# Sheet1.net
KiCad netlist of a schematic drawn in Altium Designer
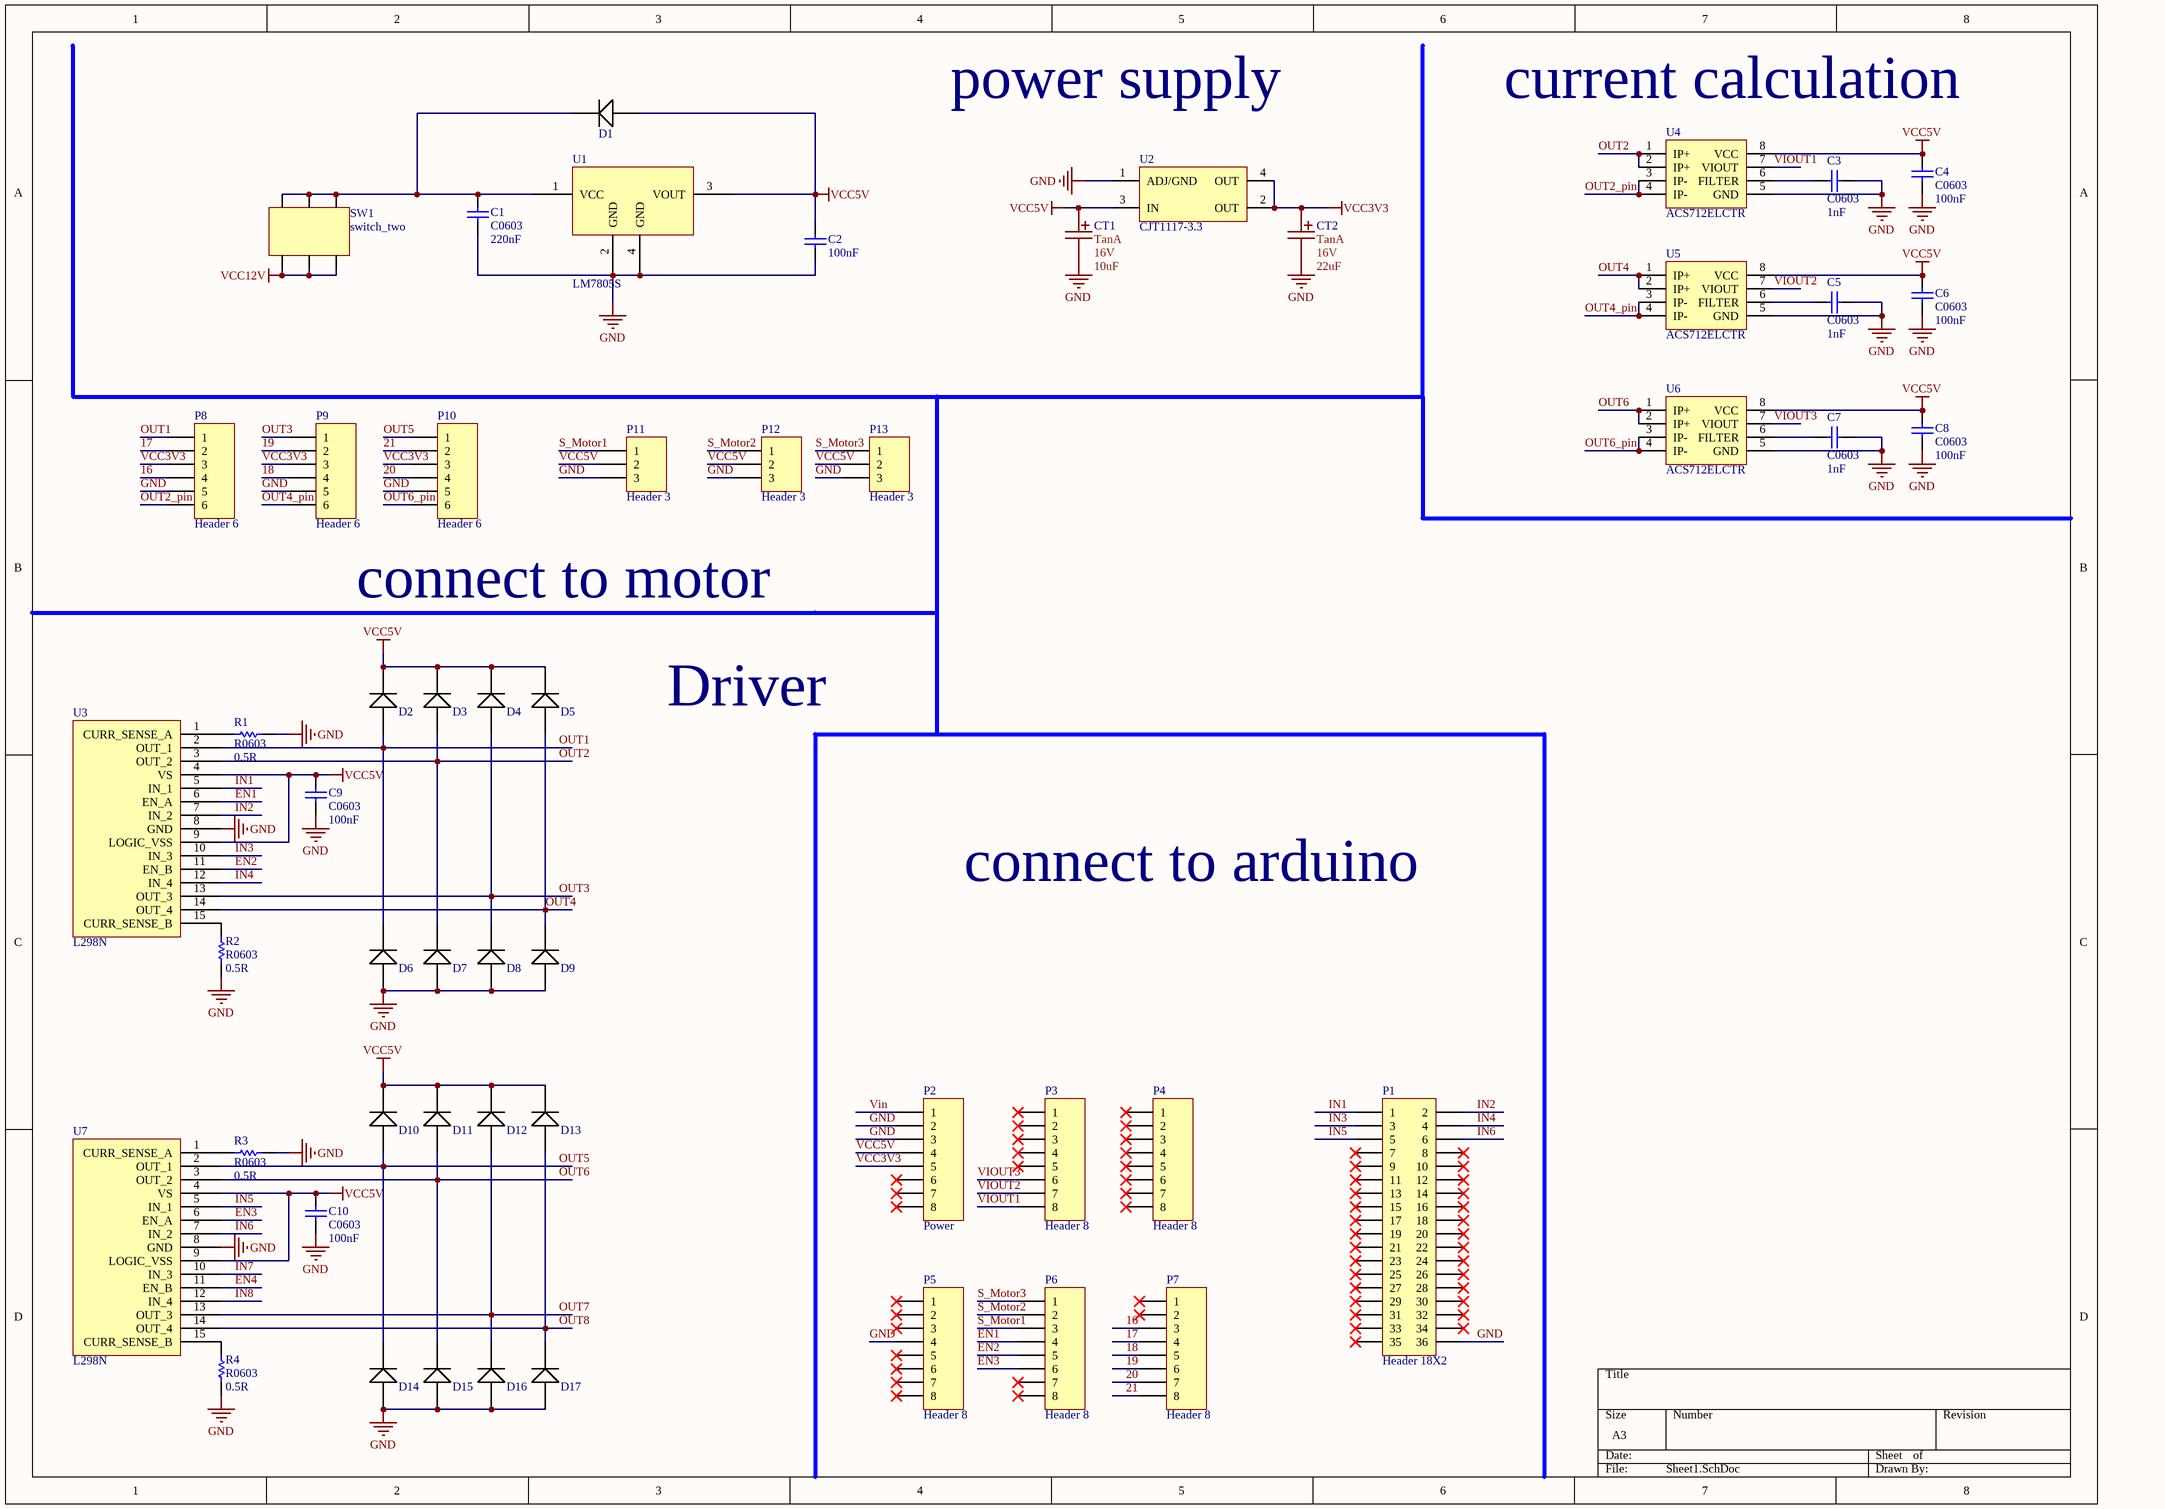
[diagram p0: Sheet1.SchDoc]

(export (version "E")
  (design (tool "Eeschema 10.0.6"))
  (components
    (comp (ref "C1")
      (value "220nF")
      (footprint "C0603_160X80X140L35N")
      (description "0603 SMT MLCC Capacitor")
      (fields
        (field (name "VOLTAGE") "50V")
        (field (name "TOLERANCE") "10%")
        (field (name "CASE/PACKAGE") "C0603")
        (field (name "PUBLISHER") "Altium Limited")
      )
      (libsource (lib "ayaya0lib") (part "Cap0603"))
    )
    (comp (ref "C2")
      (value "100nF")
      (footprint "C0402_100X50X140L30N")
      (description "SMT MLCC Capacitor")
      (fields (field (name "Comment") "Capacitor") (field (name "PUBLISHER") "Altium Limited"))
      (libsource (lib "ayayalib") (part "Cap1"))
    )
    (comp (ref "C3")
      (value "1nF")
      (footprint "C0603_160X80X140L35N")
      (description "0603 SMT MLCC Capacitor")
      (fields
        (field (name "VOLTAGE") "50V")
        (field (name "TOLERANCE") "10%")
        (field (name "CASE/PACKAGE") "C0603")
        (field (name "PUBLISHER") "Altium Limited")
      )
      (libsource (lib "ayaya0lib") (part "Cap0603"))
    )
    (comp (ref "C4")
      (value "100nF")
      (footprint "C0603_160X80X140L35N")
      (description "0603 SMT MLCC Capacitor")
      (fields
        (field (name "VOLTAGE") "50V")
        (field (name "TOLERANCE") "10%")
        (field (name "CASE/PACKAGE") "C0603")
        (field (name "PUBLISHER") "Altium Limited")
      )
      (libsource (lib "ayaya0lib") (part "Cap0603"))
    )
    (comp (ref "C5")
      (value "1nF")
      (footprint "C0603_160X80X140L35N")
      (description "0603 SMT MLCC Capacitor")
      (fields
        (field (name "VOLTAGE") "50V")
        (field (name "TOLERANCE") "10%")
        (field (name "CASE/PACKAGE") "C0603")
        (field (name "PUBLISHER") "Altium Limited")
      )
      (libsource (lib "ayaya0lib") (part "Cap0603"))
    )
    (comp (ref "C6")
      (value "100nF")
      (footprint "C0603_160X80X140L35N")
      (description "0603 SMT MLCC Capacitor")
      (fields
        (field (name "VOLTAGE") "50V")
        (field (name "TOLERANCE") "10%")
        (field (name "CASE/PACKAGE") "C0603")
        (field (name "PUBLISHER") "Altium Limited")
      )
      (libsource (lib "ayaya0lib") (part "Cap0603"))
    )
    (comp (ref "C7")
      (value "1nF")
      (footprint "C0603_160X80X140L35N")
      (description "0603 SMT MLCC Capacitor")
      (fields
        (field (name "VOLTAGE") "50V")
        (field (name "TOLERANCE") "10%")
        (field (name "CASE/PACKAGE") "C0603")
        (field (name "PUBLISHER") "Altium Limited")
      )
      (libsource (lib "ayaya0lib") (part "Cap0603"))
    )
    (comp (ref "C8")
      (value "100nF")
      (footprint "C0603_160X80X140L35N")
      (description "0603 SMT MLCC Capacitor")
      (fields
        (field (name "VOLTAGE") "50V")
        (field (name "TOLERANCE") "10%")
        (field (name "CASE/PACKAGE") "C0603")
        (field (name "PUBLISHER") "Altium Limited")
      )
      (libsource (lib "ayaya0lib") (part "Cap0603"))
    )
    (comp (ref "C9")
      (value "100nF")
      (footprint "C0603_160X80X140L35N")
      (description "0603 SMT MLCC Capacitor")
      (fields
        (field (name "VOLTAGE") "50V")
        (field (name "TOLERANCE") "10%")
        (field (name "CASE/PACKAGE") "C0603")
        (field (name "PUBLISHER") "Altium Limited")
      )
      (libsource (lib "ayaya0lib") (part "Cap0603"))
    )
    (comp (ref "C10")
      (value "100nF")
      (footprint "C0603_160X80X140L35N")
      (description "0603 SMT MLCC Capacitor")
      (fields
        (field (name "VOLTAGE") "50V")
        (field (name "TOLERANCE") "10%")
        (field (name "CASE/PACKAGE") "C0603")
        (field (name "PUBLISHER") "Altium Limited")
      )
      (libsource (lib "ayaya0lib") (part "Cap0603"))
    )
    (comp (ref "CT1")
      (value "10uF")
      (footprint "CTA_320X160X180L85X120N")
      (description "A case Tantalum Capacitors")
      (fields
        (field (name "TOLERANCE") "10%")
        (field (name "CASE/PACKAGE") "TanA")
        (field (name "VOLTAGE") "16V")
      )
      (libsource (lib "ayaya0lib") (part "Cap_TanA"))
    )
    (comp (ref "CT2")
      (value "22uF")
      (footprint "CTA_320X160X180L85X120N")
      (description "A case Tantalum Capacitors")
      (fields
        (field (name "TOLERANCE") "10%")
        (field (name "CASE/PACKAGE") "TanA")
        (field (name "VOLTAGE") "16V")
      )
      (libsource (lib "ayaya0lib") (part "Cap_TanA"))
    )
    (comp (ref "D1") (value "diode") (footprint "diode") (libsource (lib "driver_L289N") (part "diode")))
    (comp (ref "D2") (value "diode") (footprint "diode") (libsource (lib "driver_L289N") (part "diode")))
    (comp (ref "D3") (value "diode") (footprint "diode") (libsource (lib "driver_L289N") (part "diode")))
    (comp (ref "D4") (value "diode") (footprint "diode") (libsource (lib "driver_L289N") (part "diode")))
    (comp (ref "D5") (value "diode") (footprint "diode") (libsource (lib "driver_L289N") (part "diode")))
    (comp (ref "D6") (value "diode") (footprint "diode") (libsource (lib "driver_L289N") (part "diode")))
    (comp (ref "D7") (value "diode") (footprint "diode") (libsource (lib "driver_L289N") (part "diode")))
    (comp (ref "D8") (value "diode") (footprint "diode") (libsource (lib "driver_L289N") (part "diode")))
    (comp (ref "D9") (value "diode") (footprint "diode") (libsource (lib "driver_L289N") (part "diode")))
    (comp (ref "D10") (value "diode") (footprint "diode") (libsource (lib "driver_L289N") (part "diode")))
    (comp (ref "D11") (value "diode") (footprint "diode") (libsource (lib "driver_L289N") (part "diode")))
    (comp (ref "D12") (value "diode") (footprint "diode") (libsource (lib "driver_L289N") (part "diode")))
    (comp (ref "D13") (value "diode") (footprint "diode") (libsource (lib "driver_L289N") (part "diode")))
    (comp (ref "D14") (value "diode") (footprint "diode") (libsource (lib "driver_L289N") (part "diode")))
    (comp (ref "D15") (value "diode") (footprint "diode") (libsource (lib "driver_L289N") (part "diode")))
    (comp (ref "D16") (value "diode") (footprint "diode") (libsource (lib "driver_L289N") (part "diode")))
    (comp (ref "D17") (value "diode") (footprint "diode") (libsource (lib "driver_L289N") (part "diode")))
    (comp (ref "P1")
      (value "Header 18X2")
      (footprint "HDR2X18")
      (description "Header, 18-Pin, Dual row")
      (fields (field (name "PUBLISHER") "Altium Limited"))
      (libsource (lib "Miscellaneous Connectors") (part "Header 18X2"))
    )
    (comp (ref "P2")
      (value "Power")
      (footprint "HDR1X8")
      (description "Header, 8-Pin")
      (fields (field (name "PUBLISHER") "Altium Limited"))
      (libsource (lib "Miscellaneous Connectors") (part "Header 8"))
    )
    (comp (ref "P3")
      (value "Header 8")
      (footprint "HDR1X8")
      (description "Header, 8-Pin")
      (fields (field (name "PUBLISHER") "Altium Limited"))
      (libsource (lib "Miscellaneous Connectors") (part "Header 8"))
    )
    (comp (ref "P4")
      (value "Header 8")
      (footprint "HDR1X8")
      (description "Header, 8-Pin")
      (fields (field (name "PUBLISHER") "Altium Limited"))
      (libsource (lib "Miscellaneous Connectors") (part "Header 8"))
    )
    (comp (ref "P5")
      (value "Header 8")
      (footprint "HDR1X8")
      (description "Header, 8-Pin")
      (fields (field (name "PUBLISHER") "Altium Limited"))
      (libsource (lib "Miscellaneous Connectors") (part "Header 8"))
    )
    (comp (ref "P6")
      (value "Header 8")
      (footprint "HDR1X8")
      (description "Header, 8-Pin")
      (fields (field (name "PUBLISHER") "Altium Limited"))
      (libsource (lib "Miscellaneous Connectors") (part "Header 8"))
    )
    (comp (ref "P7")
      (value "Header 8")
      (footprint "HDR1X8")
      (description "Header, 8-Pin")
      (fields (field (name "PUBLISHER") "Altium Limited"))
      (libsource (lib "Miscellaneous Connectors") (part "Header 8"))
    )
    (comp (ref "P8")
      (value "Header 6")
      (footprint "HDR1X6")
      (description "Header, 6-Pin")
      (fields (field (name "PUBLISHER") "Altium Limited"))
      (libsource (lib "Miscellaneous Connectors") (part "Header 6"))
    )
    (comp (ref "P9")
      (value "Header 6")
      (footprint "HDR1X6")
      (description "Header, 6-Pin")
      (fields (field (name "PUBLISHER") "Altium Limited"))
      (libsource (lib "Miscellaneous Connectors") (part "Header 6"))
    )
    (comp (ref "P10")
      (value "Header 6")
      (footprint "HDR1X6")
      (description "Header, 6-Pin")
      (fields (field (name "PUBLISHER") "Altium Limited"))
      (libsource (lib "Miscellaneous Connectors") (part "Header 6"))
    )
    (comp (ref "P11")
      (value "Header 3")
      (footprint "HDR1X3")
      (description "Header, 3-Pin")
      (fields (field (name "PUBLISHER") "Altium Limited"))
      (libsource (lib "Miscellaneous Connectors") (part "Header 3"))
    )
    (comp (ref "P12")
      (value "Header 3")
      (footprint "HDR1X3")
      (description "Header, 3-Pin")
      (fields (field (name "PUBLISHER") "Altium Limited"))
      (libsource (lib "Miscellaneous Connectors") (part "Header 3"))
    )
    (comp (ref "P13")
      (value "Header 3")
      (footprint "HDR1X3")
      (description "Header, 3-Pin")
      (fields (field (name "PUBLISHER") "Altium Limited"))
      (libsource (lib "Miscellaneous Connectors") (part "Header 3"))
    )
    (comp (ref "R1")
      (value "0.5R")
      (footprint "R0603_160X80X140L35N")
      (description "0603 SMT Resistor")
      (fields
        (field (name "TOLERANCE") "1%")
        (field (name "CASE/PACKAGE") "R0603")
        (field (name "PUBLISHER") "Altium Limited")
      )
      (libsource (lib "ayaya0lib") (part "Res0603"))
    )
    (comp (ref "R2")
      (value "0.5R")
      (footprint "R0603_160X80X140L35N")
      (description "0603 SMT Resistor")
      (fields
        (field (name "TOLERANCE") "1%")
        (field (name "CASE/PACKAGE") "R0603")
        (field (name "PUBLISHER") "Altium Limited")
      )
      (libsource (lib "ayaya0lib") (part "Res0603"))
    )
    (comp (ref "R3")
      (value "0.5R")
      (footprint "R0603_160X80X140L35N")
      (description "0603 SMT Resistor")
      (fields
        (field (name "TOLERANCE") "1%")
        (field (name "CASE/PACKAGE") "R0603")
        (field (name "PUBLISHER") "Altium Limited")
      )
      (libsource (lib "ayaya0lib") (part "Res0603"))
    )
    (comp (ref "R4")
      (value "0.5R")
      (footprint "R0603_160X80X140L35N")
      (description "0603 SMT Resistor")
      (fields
        (field (name "TOLERANCE") "1%")
        (field (name "CASE/PACKAGE") "R0603")
        (field (name "PUBLISHER") "Altium Limited")
      )
      (libsource (lib "ayaya0lib") (part "Res0603"))
    )
    (comp (ref "SW1")
      (value "switch_two")
      (footprint "switch_two")
      (libsource (lib "driver_L289N") (part "switch_two"))
    )
    (comp (ref "U1")
      (value "LM7805S")
      (footprint "LM7805S")
      (libsource (lib "driver_L289N") (part "LM7805S"))
    )
    (comp (ref "U2")
      (value "CJT1117-3.3")
      (footprint "CJT1117")
      (libsource (lib "driver_L289N") (part "CJT1117-3.3"))
    )
    (comp (ref "U3")
      (value "L298N")
      (footprint "PCBComponent_1")
      (libsource (lib "driver_L289N") (part "L298N"))
    )
    (comp (ref "U4")
      (value "ACS712ELCTR")
      (footprint "ACS712ELCTR")
      (libsource (lib "driver_L289N") (part "ACS712ELCTR"))
    )
    (comp (ref "U5")
      (value "ACS712ELCTR")
      (footprint "ACS712ELCTR")
      (libsource (lib "driver_L289N") (part "ACS712ELCTR"))
    )
    (comp (ref "U6")
      (value "ACS712ELCTR")
      (footprint "ACS712ELCTR")
      (libsource (lib "driver_L289N") (part "ACS712ELCTR"))
    )
    (comp (ref "U7")
      (value "L298N")
      (footprint "PCBComponent_1")
      (libsource (lib "driver_L289N") (part "L298N"))
    )
  )
  (nets
    (net (code "1") (name "/16") (class "Default")
      (node (ref "P7") (pin "3") (pinfunction "3_3") (pintype "passive"))
      (node (ref "P8") (pin "4") (pinfunction "4_4") (pintype "passive"))
    )
    (net (code "2") (name "/17") (class "Default")
      (node (ref "P7") (pin "4") (pinfunction "4_4") (pintype "passive"))
      (node (ref "P8") (pin "2") (pinfunction "2_2") (pintype "passive"))
    )
    (net (code "3") (name "/18") (class "Default")
      (node (ref "P7") (pin "5") (pinfunction "5_5") (pintype "passive"))
      (node (ref "P9") (pin "4") (pinfunction "4_4") (pintype "passive"))
    )
    (net (code "4") (name "/19") (class "Default")
      (node (ref "P7") (pin "6") (pinfunction "6_6") (pintype "passive"))
      (node (ref "P9") (pin "2") (pinfunction "2_2") (pintype "passive"))
    )
    (net (code "5") (name "/20") (class "Default")
      (node (ref "P10") (pin "4") (pinfunction "4_4") (pintype "passive"))
      (node (ref "P7") (pin "7") (pinfunction "7_7") (pintype "passive"))
    )
    (net (code "6") (name "/21") (class "Default")
      (node (ref "P10") (pin "2") (pinfunction "2_2") (pintype "passive"))
      (node (ref "P7") (pin "8") (pinfunction "8_8") (pintype "passive"))
    )
    (net (code "7") (name "/EN1") (class "Default")
      (node (ref "P6") (pin "4") (pinfunction "4_4") (pintype "passive"))
      (node (ref "U3") (pin "6") (pinfunction "EN_A_6") (pintype "passive"))
    )
    (net (code "8") (name "/EN2") (class "Default")
      (node (ref "P6") (pin "5") (pinfunction "5_5") (pintype "passive"))
      (node (ref "U3") (pin "11") (pinfunction "EN_B_11") (pintype "passive"))
    )
    (net (code "9") (name "/EN3") (class "Default")
      (node (ref "P6") (pin "6") (pinfunction "6_6") (pintype "passive"))
      (node (ref "U7") (pin "6") (pinfunction "EN_A_6") (pintype "passive"))
    )
    (net (code "10") (name "/EN4") (class "Default")
      (node (ref "U7") (pin "11") (pinfunction "EN_B_11") (pintype "passive"))
    )
    (net (code "11") (name "/IN1") (class "Default")
      (node (ref "P1") (pin "1") (pinfunction "1_1") (pintype "passive"))
      (node (ref "U3") (pin "5") (pinfunction "IN_1_5") (pintype "passive"))
    )
    (net (code "12") (name "/IN2") (class "Default")
      (node (ref "P1") (pin "2") (pinfunction "2_2") (pintype "passive"))
      (node (ref "U3") (pin "7") (pinfunction "IN_2_7") (pintype "passive"))
    )
    (net (code "13") (name "/IN3") (class "Default")
      (node (ref "P1") (pin "3") (pinfunction "3_3") (pintype "passive"))
      (node (ref "U3") (pin "10") (pinfunction "IN_3_10") (pintype "passive"))
    )
    (net (code "14") (name "/IN4") (class "Default")
      (node (ref "P1") (pin "4") (pinfunction "4_4") (pintype "passive"))
      (node (ref "U3") (pin "12") (pinfunction "IN_4_12") (pintype "passive"))
    )
    (net (code "15") (name "/IN5") (class "Default")
      (node (ref "P1") (pin "5") (pinfunction "5_5") (pintype "passive"))
      (node (ref "U7") (pin "5") (pinfunction "IN_1_5") (pintype "passive"))
    )
    (net (code "16") (name "/IN6") (class "Default")
      (node (ref "P1") (pin "6") (pinfunction "6_6") (pintype "passive"))
      (node (ref "U7") (pin "7") (pinfunction "IN_2_7") (pintype "passive"))
    )
    (net (code "17") (name "/IN7") (class "Default")
      (node (ref "U7") (pin "10") (pinfunction "IN_3_10") (pintype "passive"))
    )
    (net (code "18") (name "/IN8") (class "Default")
      (node (ref "U7") (pin "12") (pinfunction "IN_4_12") (pintype "passive"))
    )
    (net (code "19") (name "/OUT1") (class "Default")
      (node (ref "D2") (pin "1") (pinfunction "-_1") (pintype "passive"))
      (node (ref "D6") (pin "2") (pinfunction "+_2") (pintype "passive"))
      (node (ref "P8") (pin "1") (pinfunction "1_1") (pintype "passive"))
      (node (ref "U3") (pin "2") (pinfunction "OUT_1_2") (pintype "passive"))
    )
    (net (code "20") (name "/OUT2") (class "Default")
      (node (ref "D3") (pin "1") (pinfunction "-_1") (pintype "passive"))
      (node (ref "D7") (pin "2") (pinfunction "+_2") (pintype "passive"))
      (node (ref "U3") (pin "3") (pinfunction "OUT_2_3") (pintype "passive"))
      (node (ref "U4") (pin "1") (pinfunction "IP+_1") (pintype "passive"))
      (node (ref "U4") (pin "2") (pinfunction "IP+_2") (pintype "passive"))
    )
    (net (code "21") (name "/OUT2_pin") (class "Default")
      (node (ref "P8") (pin "6") (pinfunction "6_6") (pintype "passive"))
      (node (ref "U4") (pin "3") (pinfunction "IP-_3") (pintype "passive"))
      (node (ref "U4") (pin "4") (pinfunction "IP-_4") (pintype "passive"))
    )
    (net (code "22") (name "/OUT3") (class "Default")
      (node (ref "D4") (pin "1") (pinfunction "-_1") (pintype "passive"))
      (node (ref "D8") (pin "2") (pinfunction "+_2") (pintype "passive"))
      (node (ref "P9") (pin "1") (pinfunction "1_1") (pintype "passive"))
      (node (ref "U3") (pin "13") (pinfunction "OUT_3_13") (pintype "passive"))
    )
    (net (code "23") (name "/OUT4") (class "Default")
      (node (ref "D5") (pin "1") (pinfunction "-_1") (pintype "passive"))
      (node (ref "D9") (pin "2") (pinfunction "+_2") (pintype "passive"))
      (node (ref "U3") (pin "14") (pinfunction "OUT_4_14") (pintype "passive"))
      (node (ref "U5") (pin "1") (pinfunction "IP+_1") (pintype "passive"))
      (node (ref "U5") (pin "2") (pinfunction "IP+_2") (pintype "passive"))
    )
    (net (code "24") (name "/OUT4_pin") (class "Default")
      (node (ref "P9") (pin "6") (pinfunction "6_6") (pintype "passive"))
      (node (ref "U5") (pin "3") (pinfunction "IP-_3") (pintype "passive"))
      (node (ref "U5") (pin "4") (pinfunction "IP-_4") (pintype "passive"))
    )
    (net (code "25") (name "/OUT5") (class "Default")
      (node (ref "D10") (pin "1") (pinfunction "-_1") (pintype "passive"))
      (node (ref "D14") (pin "2") (pinfunction "+_2") (pintype "passive"))
      (node (ref "P10") (pin "1") (pinfunction "1_1") (pintype "passive"))
      (node (ref "U7") (pin "2") (pinfunction "OUT_1_2") (pintype "passive"))
    )
    (net (code "26") (name "/OUT6") (class "Default")
      (node (ref "D11") (pin "1") (pinfunction "-_1") (pintype "passive"))
      (node (ref "D15") (pin "2") (pinfunction "+_2") (pintype "passive"))
      (node (ref "U6") (pin "1") (pinfunction "IP+_1") (pintype "passive"))
      (node (ref "U6") (pin "2") (pinfunction "IP+_2") (pintype "passive"))
      (node (ref "U7") (pin "3") (pinfunction "OUT_2_3") (pintype "passive"))
    )
    (net (code "27") (name "/OUT6_pin") (class "Default")
      (node (ref "P10") (pin "6") (pinfunction "6_6") (pintype "passive"))
      (node (ref "U6") (pin "3") (pinfunction "IP-_3") (pintype "passive"))
      (node (ref "U6") (pin "4") (pinfunction "IP-_4") (pintype "passive"))
    )
    (net (code "28") (name "/OUT7") (class "Default")
      (node (ref "D12") (pin "1") (pinfunction "-_1") (pintype "passive"))
      (node (ref "D16") (pin "2") (pinfunction "+_2") (pintype "passive"))
      (node (ref "U7") (pin "13") (pinfunction "OUT_3_13") (pintype "passive"))
    )
    (net (code "29") (name "/OUT8") (class "Default")
      (node (ref "D13") (pin "1") (pinfunction "-_1") (pintype "passive"))
      (node (ref "D17") (pin "2") (pinfunction "+_2") (pintype "passive"))
      (node (ref "U7") (pin "14") (pinfunction "OUT_4_14") (pintype "passive"))
    )
    (net (code "30") (name "/S_Motor1") (class "Default")
      (node (ref "P11") (pin "1") (pinfunction "1_1") (pintype "passive"))
      (node (ref "P6") (pin "3") (pinfunction "3_3") (pintype "passive"))
    )
    (net (code "31") (name "/S_Motor2") (class "Default")
      (node (ref "P12") (pin "1") (pinfunction "1_1") (pintype "passive"))
      (node (ref "P6") (pin "2") (pinfunction "2_2") (pintype "passive"))
    )
    (net (code "32") (name "/S_Motor3") (class "Default")
      (node (ref "P13") (pin "1") (pinfunction "1_1") (pintype "passive"))
      (node (ref "P6") (pin "1") (pinfunction "1_1") (pintype "passive"))
    )
    (net (code "33") (name "/VIOUT1") (class "Default")
      (node (ref "P3") (pin "8") (pinfunction "8_8") (pintype "passive"))
      (node (ref "U4") (pin "7") (pinfunction "VIOUT_7") (pintype "passive"))
    )
    (net (code "34") (name "/VIOUT2") (class "Default")
      (node (ref "P3") (pin "7") (pinfunction "7_7") (pintype "passive"))
      (node (ref "U5") (pin "7") (pinfunction "VIOUT_7") (pintype "passive"))
    )
    (net (code "35") (name "/VIOUT3") (class "Default")
      (node (ref "P3") (pin "6") (pinfunction "6_6") (pintype "passive"))
      (node (ref "U6") (pin "7") (pinfunction "VIOUT_7") (pintype "passive"))
    )
    (net (code "36") (name "/Vin") (class "Default")
      (node (ref "P2") (pin "1") (pinfunction "1_1") (pintype "passive"))
    )
    (net (code "37") (name "GND") (class "Default")
      (node (ref "C1") (pin "1") (pinfunction "1_1") (pintype "passive"))
      (node (ref "C10") (pin "1") (pinfunction "1_1") (pintype "passive"))
      (node (ref "C2") (pin "1") (pinfunction "1_1") (pintype "passive"))
      (node (ref "C3") (pin "1") (pinfunction "1_1") (pintype "passive"))
      (node (ref "C4") (pin "1") (pinfunction "1_1") (pintype "passive"))
      (node (ref "C5") (pin "1") (pinfunction "1_1") (pintype "passive"))
      (node (ref "C6") (pin "1") (pinfunction "1_1") (pintype "passive"))
      (node (ref "C7") (pin "1") (pinfunction "1_1") (pintype "passive"))
      (node (ref "C8") (pin "1") (pinfunction "1_1") (pintype "passive"))
      (node (ref "C9") (pin "1") (pinfunction "1_1") (pintype "passive"))
      (node (ref "CT1") (pin "2") (pinfunction "-_2") (pintype "passive"))
      (node (ref "CT2") (pin "2") (pinfunction "-_2") (pintype "passive"))
      (node (ref "D14") (pin "1") (pinfunction "-_1") (pintype "passive"))
      (node (ref "D15") (pin "1") (pinfunction "-_1") (pintype "passive"))
      (node (ref "D16") (pin "1") (pinfunction "-_1") (pintype "passive"))
      (node (ref "D17") (pin "1") (pinfunction "-_1") (pintype "passive"))
      (node (ref "D6") (pin "1") (pinfunction "-_1") (pintype "passive"))
      (node (ref "D7") (pin "1") (pinfunction "-_1") (pintype "passive"))
      (node (ref "D8") (pin "1") (pinfunction "-_1") (pintype "passive"))
      (node (ref "D9") (pin "1") (pinfunction "-_1") (pintype "passive"))
      (node (ref "P1") (pin "36") (pinfunction "36_36") (pintype "passive"))
      (node (ref "P10") (pin "5") (pinfunction "5_5") (pintype "passive"))
      (node (ref "P11") (pin "3") (pinfunction "3_3") (pintype "passive"))
      (node (ref "P12") (pin "3") (pinfunction "3_3") (pintype "passive"))
      (node (ref "P13") (pin "3") (pinfunction "3_3") (pintype "passive"))
      (node (ref "P2") (pin "2") (pinfunction "2_2") (pintype "passive"))
      (node (ref "P2") (pin "3") (pinfunction "3_3") (pintype "passive"))
      (node (ref "P5") (pin "4") (pinfunction "4_4") (pintype "passive"))
      (node (ref "P8") (pin "5") (pinfunction "5_5") (pintype "passive"))
      (node (ref "P9") (pin "5") (pinfunction "5_5") (pintype "passive"))
      (node (ref "R1") (pin "1") (pinfunction "1_1") (pintype "passive"))
      (node (ref "R2") (pin "1") (pinfunction "1_1") (pintype "passive"))
      (node (ref "R3") (pin "1") (pinfunction "1_1") (pintype "passive"))
      (node (ref "R4") (pin "1") (pinfunction "1_1") (pintype "passive"))
      (node (ref "U1") (pin "2") (pinfunction "GND_2") (pintype "passive"))
      (node (ref "U1") (pin "4") (pinfunction "GND_4") (pintype "passive"))
      (node (ref "U2") (pin "1") (pinfunction "ADJ/GND_1") (pintype "passive"))
      (node (ref "U3") (pin "8") (pinfunction "GND_8") (pintype "passive"))
      (node (ref "U4") (pin "5") (pinfunction "GND_5") (pintype "passive"))
      (node (ref "U5") (pin "5") (pinfunction "GND_5") (pintype "passive"))
      (node (ref "U6") (pin "5") (pinfunction "GND_5") (pintype "passive"))
      (node (ref "U7") (pin "8") (pinfunction "GND_8") (pintype "passive"))
    )
    (net (code "38") (name "Net-(D1-+)") (class "Default")
      (node (ref "C1") (pin "2") (pinfunction "2_2") (pintype "passive"))
      (node (ref "D1") (pin "2") (pinfunction "+_2") (pintype "passive"))
      (node (ref "SW1") (pin "1") (pinfunction "A_1") (pintype "passive"))
      (node (ref "SW1") (pin "2") (pinfunction "A_2") (pintype "passive"))
      (node (ref "SW1") (pin "3") (pinfunction "A_3") (pintype "passive"))
      (node (ref "U1") (pin "1") (pinfunction "VCC_1") (pintype "passive"))
    )
    (net (code "39") (name "Net-(U3-CURR_SENSE_A)") (class "Default")
      (node (ref "R1") (pin "2") (pinfunction "2_2") (pintype "passive"))
      (node (ref "U3") (pin "1") (pinfunction "CURR_SENSE_A_1") (pintype "passive"))
    )
    (net (code "40") (name "Net-(U3-CURR_SENSE_B)") (class "Default")
      (node (ref "R2") (pin "2") (pinfunction "2_2") (pintype "passive"))
      (node (ref "U3") (pin "15") (pinfunction "CURR_SENSE_B_15") (pintype "passive"))
    )
    (net (code "41") (name "Net-(U4-FILTER)") (class "Default")
      (node (ref "C3") (pin "2") (pinfunction "2_2") (pintype "passive"))
      (node (ref "U4") (pin "6") (pinfunction "FILTER_6") (pintype "passive"))
    )
    (net (code "42") (name "Net-(U5-FILTER)") (class "Default")
      (node (ref "C5") (pin "2") (pinfunction "2_2") (pintype "passive"))
      (node (ref "U5") (pin "6") (pinfunction "FILTER_6") (pintype "passive"))
    )
    (net (code "43") (name "Net-(U6-FILTER)") (class "Default")
      (node (ref "C7") (pin "2") (pinfunction "2_2") (pintype "passive"))
      (node (ref "U6") (pin "6") (pinfunction "FILTER_6") (pintype "passive"))
    )
    (net (code "44") (name "Net-(U7-CURR_SENSE_A)") (class "Default")
      (node (ref "R3") (pin "2") (pinfunction "2_2") (pintype "passive"))
      (node (ref "U7") (pin "1") (pinfunction "CURR_SENSE_A_1") (pintype "passive"))
    )
    (net (code "45") (name "Net-(U7-CURR_SENSE_B)") (class "Default")
      (node (ref "R4") (pin "2") (pinfunction "2_2") (pintype "passive"))
      (node (ref "U7") (pin "15") (pinfunction "CURR_SENSE_B_15") (pintype "passive"))
    )
    (net (code "46") (name "VCC3V3") (class "Default")
      (node (ref "CT2") (pin "1") (pinfunction "1_1") (pintype "passive"))
      (node (ref "P10") (pin "3") (pinfunction "3_3") (pintype "passive"))
      (node (ref "P2") (pin "5") (pinfunction "5_5") (pintype "passive"))
      (node (ref "P8") (pin "3") (pinfunction "3_3") (pintype "passive"))
      (node (ref "P9") (pin "3") (pinfunction "3_3") (pintype "passive"))
      (node (ref "U2") (pin "2") (pinfunction "OUT_2") (pintype "passive"))
      (node (ref "U2") (pin "4") (pinfunction "OUT_4") (pintype "passive"))
    )
    (net (code "47") (name "VCC5V") (class "Default")
      (node (ref "C10") (pin "2") (pinfunction "2_2") (pintype "passive"))
      (node (ref "C2") (pin "2") (pinfunction "2_2") (pintype "passive"))
      (node (ref "C4") (pin "2") (pinfunction "2_2") (pintype "passive"))
      (node (ref "C6") (pin "2") (pinfunction "2_2") (pintype "passive"))
      (node (ref "C8") (pin "2") (pinfunction "2_2") (pintype "passive"))
      (node (ref "C9") (pin "2") (pinfunction "2_2") (pintype "passive"))
      (node (ref "CT1") (pin "1") (pinfunction "1_1") (pintype "passive"))
      (node (ref "D1") (pin "1") (pinfunction "-_1") (pintype "passive"))
      (node (ref "D10") (pin "2") (pinfunction "+_2") (pintype "passive"))
      (node (ref "D11") (pin "2") (pinfunction "+_2") (pintype "passive"))
      (node (ref "D12") (pin "2") (pinfunction "+_2") (pintype "passive"))
      (node (ref "D13") (pin "2") (pinfunction "+_2") (pintype "passive"))
      (node (ref "D2") (pin "2") (pinfunction "+_2") (pintype "passive"))
      (node (ref "D3") (pin "2") (pinfunction "+_2") (pintype "passive"))
      (node (ref "D4") (pin "2") (pinfunction "+_2") (pintype "passive"))
      (node (ref "D5") (pin "2") (pinfunction "+_2") (pintype "passive"))
      (node (ref "P11") (pin "2") (pinfunction "2_2") (pintype "passive"))
      (node (ref "P12") (pin "2") (pinfunction "2_2") (pintype "passive"))
      (node (ref "P13") (pin "2") (pinfunction "2_2") (pintype "passive"))
      (node (ref "P2") (pin "4") (pinfunction "4_4") (pintype "passive"))
      (node (ref "U1") (pin "3") (pinfunction "VOUT_3") (pintype "passive"))
      (node (ref "U2") (pin "3") (pinfunction "IN_3") (pintype "passive"))
      (node (ref "U3") (pin "4") (pinfunction "VS_4") (pintype "passive"))
      (node (ref "U3") (pin "9") (pinfunction "LOGIC_VSS_9") (pintype "passive"))
      (node (ref "U4") (pin "8") (pinfunction "VCC_8") (pintype "passive"))
      (node (ref "U5") (pin "8") (pinfunction "VCC_8") (pintype "passive"))
      (node (ref "U6") (pin "8") (pinfunction "VCC_8") (pintype "passive"))
      (node (ref "U7") (pin "4") (pinfunction "VS_4") (pintype "passive"))
      (node (ref "U7") (pin "9") (pinfunction "LOGIC_VSS_9") (pintype "passive"))
    )
    (net (code "48") (name "VCC12V") (class "Default")
      (node (ref "SW1") (pin "4") (pinfunction "A_4") (pintype "passive"))
      (node (ref "SW1") (pin "5") (pinfunction "A_5") (pintype "passive"))
      (node (ref "SW1") (pin "6") (pinfunction "A_6") (pintype "passive"))
    )
    (net (code "49") (name "unconnected-(P1-Pad7)") (class "Default")
      (node (ref "P1") (pin "7") (pinfunction "7_7") (pintype "passive+no_connect"))
    )
    (net (code "50") (name "unconnected-(P1-Pad8)") (class "Default")
      (node (ref "P1") (pin "8") (pinfunction "8_8") (pintype "passive+no_connect"))
    )
    (net (code "51") (name "unconnected-(P1-Pad9)") (class "Default")
      (node (ref "P1") (pin "9") (pinfunction "9_9") (pintype "passive+no_connect"))
    )
    (net (code "52") (name "unconnected-(P1-Pad10)") (class "Default")
      (node (ref "P1") (pin "10") (pinfunction "10_10") (pintype "passive+no_connect"))
    )
    (net (code "53") (name "unconnected-(P1-Pad11)") (class "Default")
      (node (ref "P1") (pin "11") (pinfunction "11_11") (pintype "passive+no_connect"))
    )
    (net (code "54") (name "unconnected-(P1-Pad12)") (class "Default")
      (node (ref "P1") (pin "12") (pinfunction "12_12") (pintype "passive+no_connect"))
    )
    (net (code "55") (name "unconnected-(P1-Pad13)") (class "Default")
      (node (ref "P1") (pin "13") (pinfunction "13_13") (pintype "passive+no_connect"))
    )
    (net (code "56") (name "unconnected-(P1-Pad14)") (class "Default")
      (node (ref "P1") (pin "14") (pinfunction "14_14") (pintype "passive+no_connect"))
    )
    (net (code "57") (name "unconnected-(P1-Pad15)") (class "Default")
      (node (ref "P1") (pin "15") (pinfunction "15_15") (pintype "passive+no_connect"))
    )
    (net (code "58") (name "unconnected-(P1-Pad16)") (class "Default")
      (node (ref "P1") (pin "16") (pinfunction "16_16") (pintype "passive+no_connect"))
    )
    (net (code "59") (name "unconnected-(P1-Pad17)") (class "Default")
      (node (ref "P1") (pin "17") (pinfunction "17_17") (pintype "passive+no_connect"))
    )
    (net (code "60") (name "unconnected-(P1-Pad18)") (class "Default")
      (node (ref "P1") (pin "18") (pinfunction "18_18") (pintype "passive+no_connect"))
    )
    (net (code "61") (name "unconnected-(P1-Pad19)") (class "Default")
      (node (ref "P1") (pin "19") (pinfunction "19_19") (pintype "passive+no_connect"))
    )
    (net (code "62") (name "unconnected-(P1-Pad20)") (class "Default")
      (node (ref "P1") (pin "20") (pinfunction "20_20") (pintype "passive+no_connect"))
    )
    (net (code "63") (name "unconnected-(P1-Pad21)") (class "Default")
      (node (ref "P1") (pin "21") (pinfunction "21_21") (pintype "passive+no_connect"))
    )
    (net (code "64") (name "unconnected-(P1-Pad22)") (class "Default")
      (node (ref "P1") (pin "22") (pinfunction "22_22") (pintype "passive+no_connect"))
    )
    (net (code "65") (name "unconnected-(P1-Pad23)") (class "Default")
      (node (ref "P1") (pin "23") (pinfunction "23_23") (pintype "passive+no_connect"))
    )
    (net (code "66") (name "unconnected-(P1-Pad24)") (class "Default")
      (node (ref "P1") (pin "24") (pinfunction "24_24") (pintype "passive+no_connect"))
    )
    (net (code "67") (name "unconnected-(P1-Pad25)") (class "Default")
      (node (ref "P1") (pin "25") (pinfunction "25_25") (pintype "passive+no_connect"))
    )
    (net (code "68") (name "unconnected-(P1-Pad26)") (class "Default")
      (node (ref "P1") (pin "26") (pinfunction "26_26") (pintype "passive+no_connect"))
    )
    (net (code "69") (name "unconnected-(P1-Pad27)") (class "Default")
      (node (ref "P1") (pin "27") (pinfunction "27_27") (pintype "passive+no_connect"))
    )
    (net (code "70") (name "unconnected-(P1-Pad28)") (class "Default")
      (node (ref "P1") (pin "28") (pinfunction "28_28") (pintype "passive+no_connect"))
    )
    (net (code "71") (name "unconnected-(P1-Pad29)") (class "Default")
      (node (ref "P1") (pin "29") (pinfunction "29_29") (pintype "passive+no_connect"))
    )
    (net (code "72") (name "unconnected-(P1-Pad30)") (class "Default")
      (node (ref "P1") (pin "30") (pinfunction "30_30") (pintype "passive+no_connect"))
    )
    (net (code "73") (name "unconnected-(P1-Pad31)") (class "Default")
      (node (ref "P1") (pin "31") (pinfunction "31_31") (pintype "passive+no_connect"))
    )
    (net (code "74") (name "unconnected-(P1-Pad32)") (class "Default")
      (node (ref "P1") (pin "32") (pinfunction "32_32") (pintype "passive+no_connect"))
    )
    (net (code "75") (name "unconnected-(P1-Pad33)") (class "Default")
      (node (ref "P1") (pin "33") (pinfunction "33_33") (pintype "passive+no_connect"))
    )
    (net (code "76") (name "unconnected-(P1-Pad34)") (class "Default")
      (node (ref "P1") (pin "34") (pinfunction "34_34") (pintype "passive+no_connect"))
    )
    (net (code "77") (name "unconnected-(P1-Pad35)") (class "Default")
      (node (ref "P1") (pin "35") (pinfunction "35_35") (pintype "passive+no_connect"))
    )
    (net (code "78") (name "unconnected-(P2-Pad6)") (class "Default")
      (node (ref "P2") (pin "6") (pinfunction "6_6") (pintype "passive+no_connect"))
    )
    (net (code "79") (name "unconnected-(P2-Pad7)") (class "Default")
      (node (ref "P2") (pin "7") (pinfunction "7_7") (pintype "passive+no_connect"))
    )
    (net (code "80") (name "unconnected-(P2-Pad8)") (class "Default")
      (node (ref "P2") (pin "8") (pinfunction "8_8") (pintype "passive+no_connect"))
    )
    (net (code "81") (name "unconnected-(P3-Pad1)") (class "Default")
      (node (ref "P3") (pin "1") (pinfunction "1_1") (pintype "passive+no_connect"))
    )
    (net (code "82") (name "unconnected-(P3-Pad2)") (class "Default")
      (node (ref "P3") (pin "2") (pinfunction "2_2") (pintype "passive+no_connect"))
    )
    (net (code "83") (name "unconnected-(P3-Pad3)") (class "Default")
      (node (ref "P3") (pin "3") (pinfunction "3_3") (pintype "passive+no_connect"))
    )
    (net (code "84") (name "unconnected-(P3-Pad4)") (class "Default")
      (node (ref "P3") (pin "4") (pinfunction "4_4") (pintype "passive+no_connect"))
    )
    (net (code "85") (name "unconnected-(P3-Pad5)") (class "Default")
      (node (ref "P3") (pin "5") (pinfunction "5_5") (pintype "passive+no_connect"))
    )
    (net (code "86") (name "unconnected-(P4-Pad1)") (class "Default")
      (node (ref "P4") (pin "1") (pinfunction "1_1") (pintype "passive+no_connect"))
    )
    (net (code "87") (name "unconnected-(P4-Pad2)") (class "Default")
      (node (ref "P4") (pin "2") (pinfunction "2_2") (pintype "passive+no_connect"))
    )
    (net (code "88") (name "unconnected-(P4-Pad3)") (class "Default")
      (node (ref "P4") (pin "3") (pinfunction "3_3") (pintype "passive+no_connect"))
    )
    (net (code "89") (name "unconnected-(P4-Pad4)") (class "Default")
      (node (ref "P4") (pin "4") (pinfunction "4_4") (pintype "passive+no_connect"))
    )
    (net (code "90") (name "unconnected-(P4-Pad5)") (class "Default")
      (node (ref "P4") (pin "5") (pinfunction "5_5") (pintype "passive+no_connect"))
    )
    (net (code "91") (name "unconnected-(P4-Pad6)") (class "Default")
      (node (ref "P4") (pin "6") (pinfunction "6_6") (pintype "passive+no_connect"))
    )
    (net (code "92") (name "unconnected-(P4-Pad7)") (class "Default")
      (node (ref "P4") (pin "7") (pinfunction "7_7") (pintype "passive+no_connect"))
    )
    (net (code "93") (name "unconnected-(P4-Pad8)") (class "Default")
      (node (ref "P4") (pin "8") (pinfunction "8_8") (pintype "passive+no_connect"))
    )
    (net (code "94") (name "unconnected-(P5-Pad1)") (class "Default")
      (node (ref "P5") (pin "1") (pinfunction "1_1") (pintype "passive+no_connect"))
    )
    (net (code "95") (name "unconnected-(P5-Pad2)") (class "Default")
      (node (ref "P5") (pin "2") (pinfunction "2_2") (pintype "passive+no_connect"))
    )
    (net (code "96") (name "unconnected-(P5-Pad3)") (class "Default")
      (node (ref "P5") (pin "3") (pinfunction "3_3") (pintype "passive+no_connect"))
    )
    (net (code "97") (name "unconnected-(P5-Pad5)") (class "Default")
      (node (ref "P5") (pin "5") (pinfunction "5_5") (pintype "passive+no_connect"))
    )
    (net (code "98") (name "unconnected-(P5-Pad6)") (class "Default")
      (node (ref "P5") (pin "6") (pinfunction "6_6") (pintype "passive+no_connect"))
    )
    (net (code "99") (name "unconnected-(P5-Pad7)") (class "Default")
      (node (ref "P5") (pin "7") (pinfunction "7_7") (pintype "passive+no_connect"))
    )
    (net (code "100") (name "unconnected-(P5-Pad8)") (class "Default")
      (node (ref "P5") (pin "8") (pinfunction "8_8") (pintype "passive+no_connect"))
    )
    (net (code "101") (name "unconnected-(P6-Pad7)") (class "Default")
      (node (ref "P6") (pin "7") (pinfunction "7_7") (pintype "passive+no_connect"))
    )
    (net (code "102") (name "unconnected-(P6-Pad8)") (class "Default")
      (node (ref "P6") (pin "8") (pinfunction "8_8") (pintype "passive+no_connect"))
    )
    (net (code "103") (name "unconnected-(P7-Pad1)") (class "Default")
      (node (ref "P7") (pin "1") (pinfunction "1_1") (pintype "passive+no_connect"))
    )
    (net (code "104") (name "unconnected-(P7-Pad2)") (class "Default")
      (node (ref "P7") (pin "2") (pinfunction "2_2") (pintype "passive+no_connect"))
    )
  )
)
